# FanController.net
KiCad netlist of a schematic drawn in Altium Designer
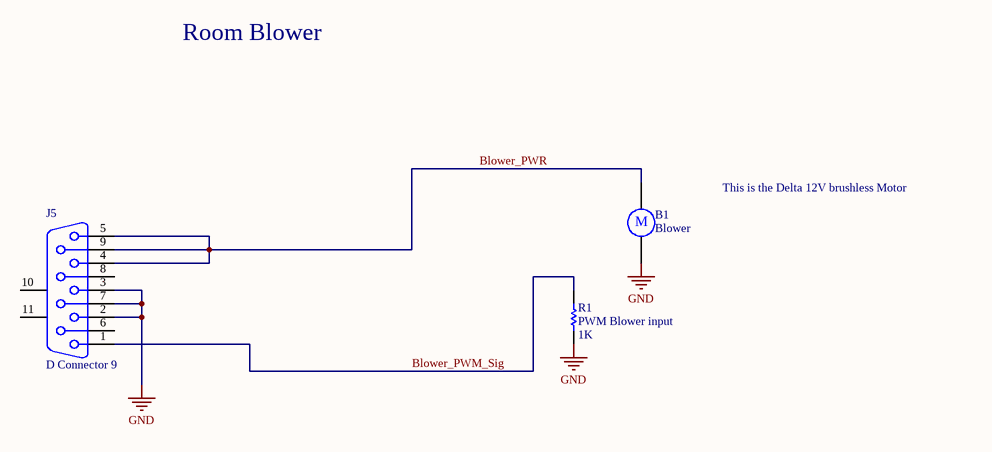
[diagram p0: FanController.SchDoc]

(export (version "E")
  (design (tool "Eeschema 10.0.6"))
  (components
    (comp (ref "B1")
      (value "Blower")
      (footprint "RB5-10.5")
      (description "Motor, General Kind")
      (fields (field (name "PUBLISHER") "Altium Limited"))
      (libsource (lib "Miscellaneous Devices") (part "Motor"))
    )
    (comp (ref "J5")
      (value "D Connector 9")
      (footprint "DSUB1.385-2H9")
      (description "Receptacle Assembly, 9 Position, Right Angle")
      (fields (field (name "PUBLISHER") "Altium Limited"))
      (libsource (lib "Miscellaneous Connectors") (part "D Connector 9"))
    )
    (comp (ref "R1")
      (value "PWM Blower input")
      (footprint "AXIAL-0.3")
      (description "Resistor")
      (fields (field (name "ALTIUM_VALUE") "1K") (field (name "PUBLISHER") "Altium Limited"))
      (libsource (lib "Miscellaneous Devices") (part "Res1"))
    )
  )
  (nets
    (net (code "1") (name "/Blower_PWM_Sig") (class "Default")
      (node (ref "J5") (pin "1") (pinfunction "1_1") (pintype "passive"))
      (node (ref "R1") (pin "2") (pinfunction "2_2") (pintype "passive"))
    )
    (net (code "2") (name "/Blower_PWR") (class "Default")
      (node (ref "B1") (pin "1") (pinfunction "1_1") (pintype "passive"))
      (node (ref "J5") (pin "4") (pinfunction "4_4") (pintype "passive"))
      (node (ref "J5") (pin "5") (pinfunction "5_5") (pintype "passive"))
      (node (ref "J5") (pin "9") (pinfunction "9_9") (pintype "passive"))
    )
    (net (code "3") (name "GND") (class "Default")
      (node (ref "B1") (pin "2") (pinfunction "2_2") (pintype "passive"))
      (node (ref "J5") (pin "2") (pinfunction "2_2") (pintype "passive"))
      (node (ref "J5") (pin "3") (pinfunction "3_3") (pintype "passive"))
      (node (ref "J5") (pin "7") (pinfunction "7_7") (pintype "passive"))
      (node (ref "R1") (pin "1") (pinfunction "1_1") (pintype "passive"))
    )
    (net (code "4") (name "unconnected-(J5-MH1-Pad10)") (class "Default")
      (node (ref "J5") (pin "10") (pinfunction "MH1_10") (pintype "passive"))
    )
    (net (code "5") (name "unconnected-(J5-MH2-Pad11)") (class "Default")
      (node (ref "J5") (pin "11") (pinfunction "MH2_11") (pintype "passive"))
    )
    (net (code "6") (name "unconnected-(J5-Pad6)") (class "Default")
      (node (ref "J5") (pin "6") (pinfunction "6_6") (pintype "passive"))
    )
    (net (code "7") (name "unconnected-(J5-Pad8)") (class "Default")
      (node (ref "J5") (pin "8") (pinfunction "8_8") (pintype "passive"))
    )
  )
)
